# ADAS_schematic.net
KiCad netlist of a schematic drawn in EAGLE
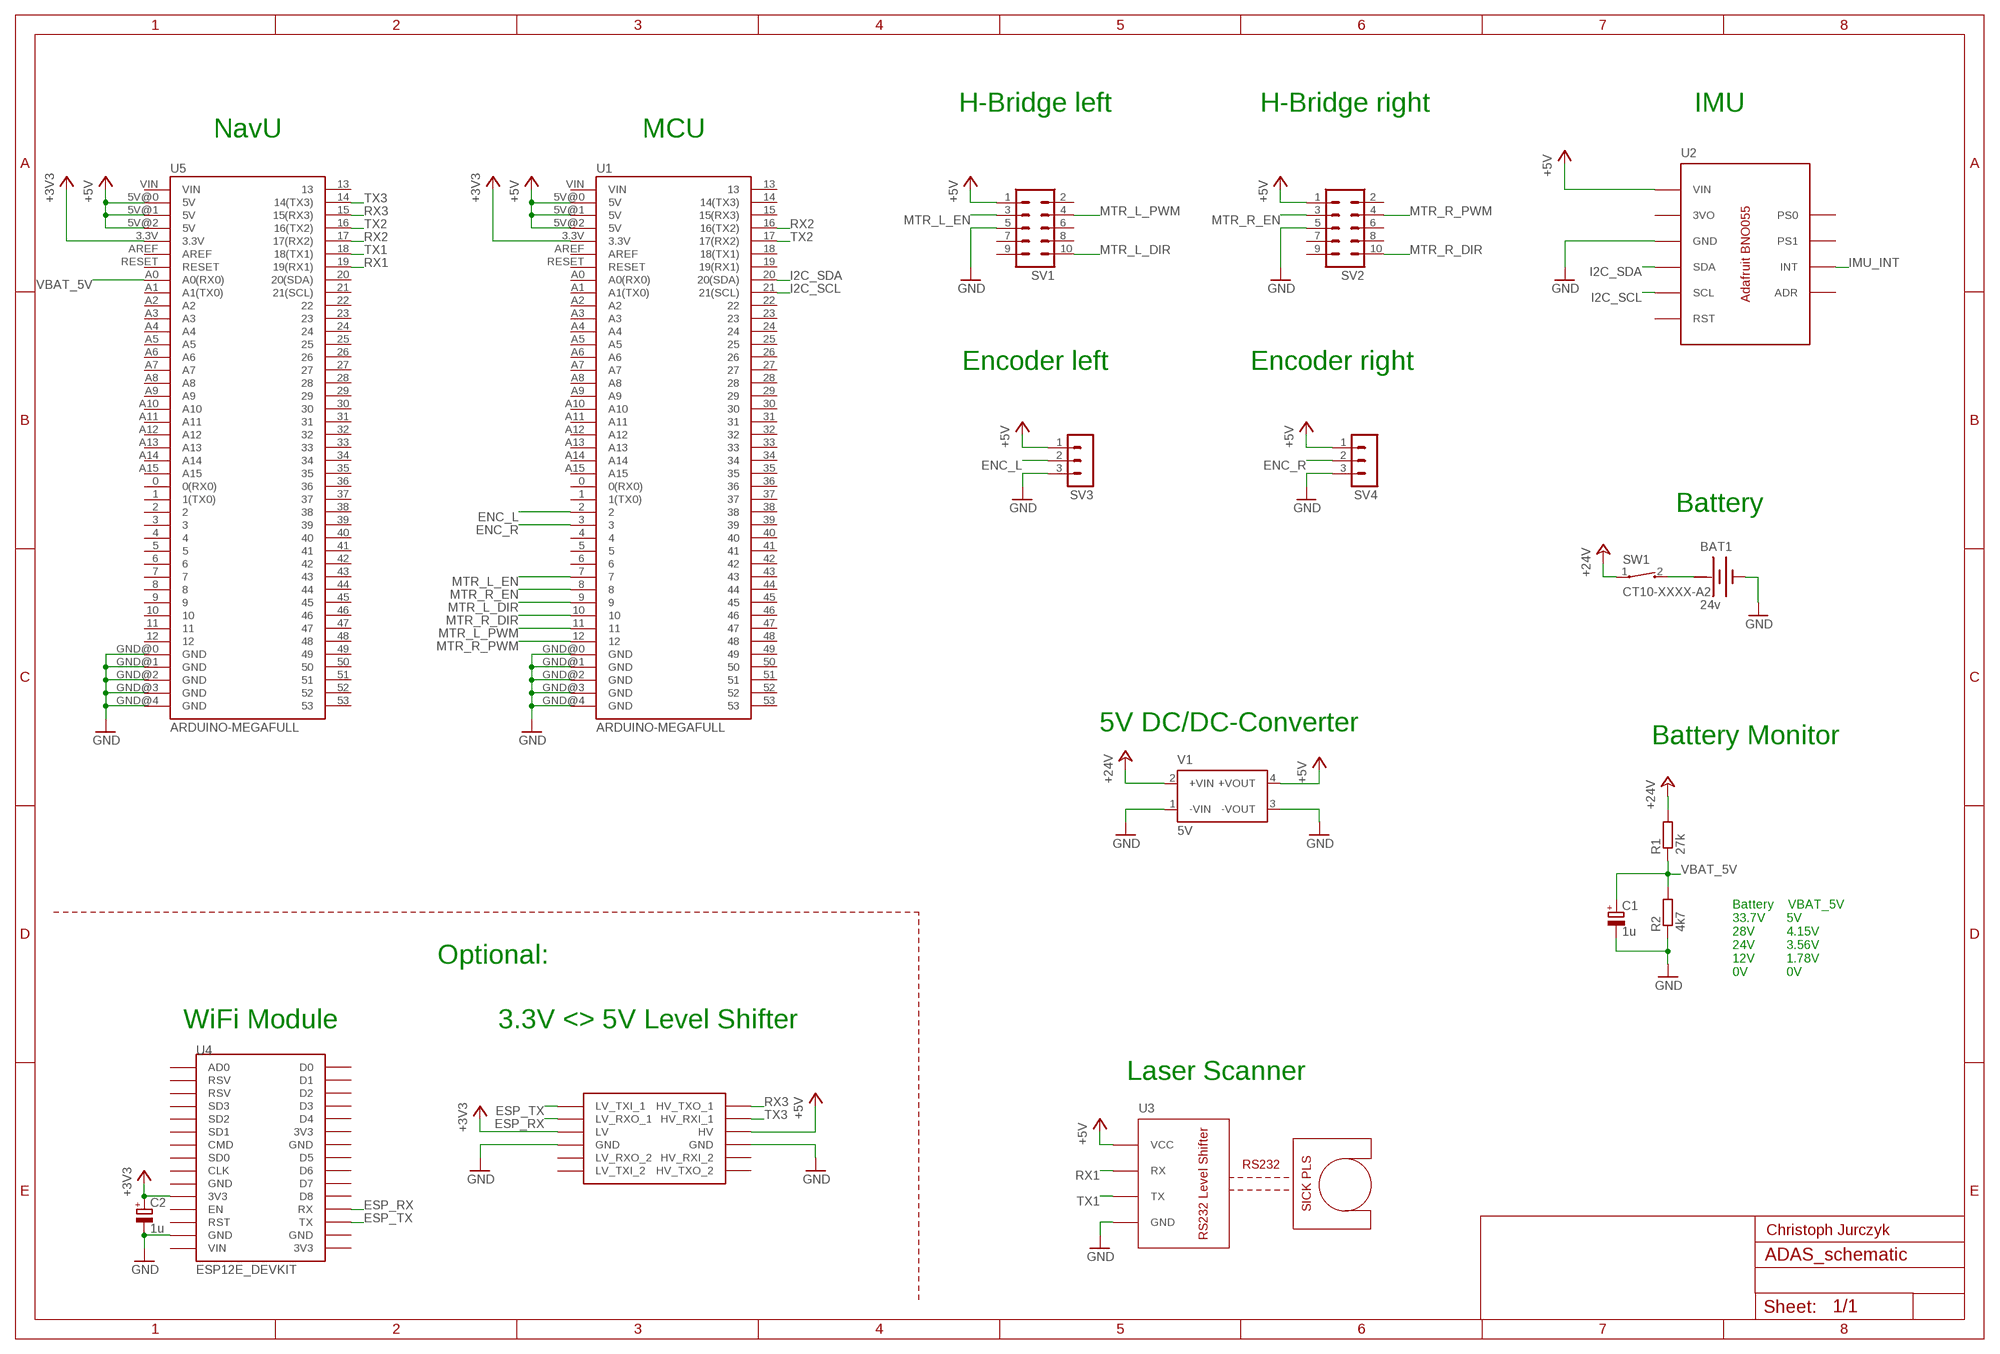
[diagram p0: schematic, sheet 1]

(export (version "E")
  (design (tool "Eeschema 10.0.6"))
  (components
    (comp (ref "BAT1")
      (value "24v")
      (footprint "eagle-import:BATTERY")
      (libsource (lib "eagle-import") (part "BATTERY"))
    )
    (comp (ref "C1")
      (value "1u")
      (footprint "eagle-import:139CLL-3R")
      (libsource (lib "eagle-import") (part "CPOL-EU139CLL-3R"))
    )
    (comp (ref "C2")
      (value "1u")
      (footprint "eagle-import:139CLL-3R")
      (libsource (lib "eagle-import") (part "CPOL-EU139CLL-3R"))
    )
    (comp (ref "R1")
      (value "27k")
      (footprint "eagle-import:0617_22")
      (libsource (lib "eagle-import") (part "R-EU_0617/22"))
    )
    (comp (ref "R2")
      (value "4k7")
      (footprint "eagle-import:0617_22")
      (libsource (lib "eagle-import") (part "R-EU_0617/22"))
    )
    (comp (ref "SV1")
      (value "ML10")
      (footprint "eagle-import:ML10")
      (libsource (lib "eagle-import") (part "ML10"))
    )
    (comp (ref "SV2")
      (value "ML10")
      (footprint "eagle-import:ML10")
      (libsource (lib "eagle-import") (part "ML10"))
    )
    (comp (ref "SV3")
      (value "MA03-1")
      (footprint "eagle-import:MA03-1")
      (libsource (lib "eagle-import") (part "MA03-1"))
    )
    (comp (ref "SV4")
      (value "MA03-1")
      (footprint "eagle-import:MA03-1")
      (libsource (lib "eagle-import") (part "MA03-1"))
    )
    (comp (ref "SW1")
      (value "CT10-XXXX-A2")
      (footprint "eagle-import:CT10-XXXX-A2")
      (libsource (lib "eagle-import") (part "CT10-XXXX-A2"))
    )
    (comp (ref "U$2")
      (value "LOGIC_LEVEL_CONVERTER")
      (footprint "eagle-import:LOGIC_LEVEL_CONVERTER")
      (libsource (lib "eagle-import") (part "LOGIC_LEVEL_CONVERTER"))
    )
    (comp (ref "U1")
      (value "ARDUINO-MEGAFULL")
      (footprint "eagle-import:ARDUINO_MEGA")
      (libsource (lib "eagle-import") (part "ARDUINO-MEGAFULL"))
    )
    (comp (ref "U2")
      (value "ADAFRUIT_BNO055")
      (footprint "eagle-import:DUMMY")
      (libsource (lib "eagle-import") (part "ADAFRUIT_BNO055"))
    )
    (comp (ref "U3")
      (value "SICK_PLS")
      (footprint "eagle-import:DUMMY")
      (libsource (lib "eagle-import") (part "SICK_PLS"))
    )
    (comp (ref "U4")
      (value "ESP12E_DEVKIT")
      (footprint "eagle-import:ESP12E_DEVKIT")
      (libsource (lib "eagle-import") (part "ESP12E_DEVKIT"))
    )
    (comp (ref "U5")
      (value "ARDUINO-MEGAFULL")
      (footprint "eagle-import:ARDUINO_MEGA")
      (libsource (lib "eagle-import") (part "ARDUINO-MEGAFULL"))
    )
    (comp (ref "V1")
      (value "5V")
      (footprint "eagle-import:TME")
      (fields (field (name "MPN") "TME 0505S"))
      (libsource (lib "eagle-import") (part "TME?0505S"))
    )
  )
  (nets
    (net (code "1") (name "+3V3") (class "Default")
      (node (ref "C2") (pin "+") (pinfunction "+_+") (pintype "passive"))
      (node (ref "U$2") (pin "P$3") (pinfunction "LV_P$3") (pintype "bidirectional"))
      (node (ref "U1") (pin "3.3V") (pinfunction "3.3V_3.3V") (pintype "bidirectional"))
      (node (ref "U4") (pin "3V3@0") (pinfunction "3V3_3V3@0") (pintype "bidirectional"))
      (node (ref "U5") (pin "3.3V") (pinfunction "3.3V_3.3V") (pintype "bidirectional"))
    )
    (net (code "2") (name "+5V") (class "Default")
      (node (ref "SV1") (pin "1") (pinfunction "1_1") (pintype "passive"))
      (node (ref "SV2") (pin "1") (pinfunction "1_1") (pintype "passive"))
      (node (ref "SV3") (pin "1") (pinfunction "1_1") (pintype "passive"))
      (node (ref "SV4") (pin "1") (pinfunction "1_1") (pintype "passive"))
      (node (ref "U$2") (pin "P$10") (pinfunction "HV_P$10") (pintype "bidirectional"))
      (node (ref "U1") (pin "5V@0") (pinfunction "5V_5V@0") (pintype "bidirectional"))
      (node (ref "U1") (pin "5V@1") (pinfunction "5V_5V@1") (pintype "bidirectional"))
      (node (ref "U1") (pin "5V@2") (pinfunction "5V_5V@2") (pintype "bidirectional"))
      (node (ref "U2") (pin "P$10") (pinfunction "VIN_P$10") (pintype "bidirectional"))
      (node (ref "U3") (pin "P$4") (pinfunction "VCC_P$4") (pintype "bidirectional"))
      (node (ref "U5") (pin "5V@0") (pinfunction "5V_5V@0") (pintype "bidirectional"))
      (node (ref "U5") (pin "5V@1") (pinfunction "5V_5V@1") (pintype "bidirectional"))
      (node (ref "U5") (pin "5V@2") (pinfunction "5V_5V@2") (pintype "bidirectional"))
      (node (ref "V1") (pin "4") (pinfunction "+VOUT_4") (pintype "passive"))
    )
    (net (code "3") (name "+24V") (class "Default")
      (node (ref "R1") (pin "2") (pinfunction "2_2") (pintype "passive"))
      (node (ref "SW1") (pin "1") (pinfunction "1_1") (pintype "passive"))
      (node (ref "V1") (pin "2") (pinfunction "+VIN_2") (pintype "passive"))
    )
    (net (code "4") (name "/+") (class "Default")
      (node (ref "BAT1") (pin "+@1") (pinfunction "+_+@1") (pintype "power_in"))
    )
    (net (code "5") (name "/ENC_L") (class "Default")
      (node (ref "SV3") (pin "2") (pinfunction "2_2") (pintype "passive"))
      (node (ref "U1") (pin "2") (pinfunction "2_2") (pintype "bidirectional"))
    )
    (net (code "6") (name "/ENC_R") (class "Default")
      (node (ref "SV4") (pin "2") (pinfunction "2_2") (pintype "passive"))
      (node (ref "U1") (pin "3") (pinfunction "3_3") (pintype "bidirectional"))
    )
    (net (code "7") (name "/ESP_RX") (class "Default")
      (node (ref "U$2") (pin "P$2") (pinfunction "LV_RXO_1_P$2") (pintype "bidirectional"))
      (node (ref "U4") (pin "RX") (pinfunction "RX_RX") (pintype "bidirectional"))
    )
    (net (code "8") (name "/ESP_TX") (class "Default")
      (node (ref "U$2") (pin "P$1") (pinfunction "LV_TXI_1_P$1") (pintype "bidirectional"))
      (node (ref "U4") (pin "TX") (pinfunction "TX_TX") (pintype "bidirectional"))
    )
    (net (code "9") (name "/I2C_SCL") (class "Default")
      (node (ref "U1") (pin "21") (pinfunction "21(SCL)_21") (pintype "bidirectional"))
      (node (ref "U2") (pin "P$8") (pinfunction "SCL_P$8") (pintype "bidirectional"))
    )
    (net (code "10") (name "/I2C_SDA") (class "Default")
      (node (ref "U1") (pin "20") (pinfunction "20(SDA)_20") (pintype "bidirectional"))
      (node (ref "U2") (pin "P$9") (pinfunction "SDA_P$9") (pintype "bidirectional"))
    )
    (net (code "11") (name "/IMU_INT") (class "Default")
      (node (ref "U2") (pin "P$4") (pinfunction "INT_P$4") (pintype "bidirectional"))
    )
    (net (code "12") (name "/MTR_L_DIR") (class "Default")
      (node (ref "SV1") (pin "10") (pinfunction "10_10") (pintype "passive"))
      (node (ref "U1") (pin "9") (pinfunction "9_9") (pintype "bidirectional"))
    )
    (net (code "13") (name "/MTR_L_EN") (class "Default")
      (node (ref "SV1") (pin "3") (pinfunction "3_3") (pintype "passive"))
      (node (ref "U1") (pin "7") (pinfunction "7_7") (pintype "bidirectional"))
    )
    (net (code "14") (name "/MTR_L_PWM") (class "Default")
      (node (ref "SV1") (pin "4") (pinfunction "4_4") (pintype "passive"))
      (node (ref "U1") (pin "11") (pinfunction "11_11") (pintype "bidirectional"))
    )
    (net (code "15") (name "/MTR_R_DIR") (class "Default")
      (node (ref "SV2") (pin "10") (pinfunction "10_10") (pintype "passive"))
      (node (ref "U1") (pin "10") (pinfunction "10_10") (pintype "bidirectional"))
    )
    (net (code "16") (name "/MTR_R_EN") (class "Default")
      (node (ref "SV2") (pin "3") (pinfunction "3_3") (pintype "passive"))
      (node (ref "U1") (pin "8") (pinfunction "8_8") (pintype "bidirectional"))
    )
    (net (code "17") (name "/MTR_R_PWM") (class "Default")
      (node (ref "SV2") (pin "4") (pinfunction "4_4") (pintype "passive"))
      (node (ref "U1") (pin "12") (pinfunction "12_12") (pintype "bidirectional"))
    )
    (net (code "18") (name "/RX1") (class "Default")
      (node (ref "U3") (pin "P$2") (pinfunction "RX_P$2") (pintype "bidirectional"))
      (node (ref "U5") (pin "19") (pinfunction "19(RX1)_19") (pintype "bidirectional"))
    )
    (net (code "19") (name "/RX2") (class "Default")
      (node (ref "U1") (pin "16") (pinfunction "16(TX2)_16") (pintype "bidirectional"))
      (node (ref "U5") (pin "17") (pinfunction "17(RX2)_17") (pintype "bidirectional"))
    )
    (net (code "20") (name "/RX3") (class "Default")
      (node (ref "U$2") (pin "P$12") (pinfunction "HV_TXO_1_P$12") (pintype "bidirectional"))
      (node (ref "U5") (pin "15") (pinfunction "15(RX3)_15") (pintype "bidirectional"))
    )
    (net (code "21") (name "/TX1") (class "Default")
      (node (ref "U3") (pin "P$3") (pinfunction "TX_P$3") (pintype "bidirectional"))
      (node (ref "U5") (pin "18") (pinfunction "18(TX1)_18") (pintype "bidirectional"))
    )
    (net (code "22") (name "/TX2") (class "Default")
      (node (ref "U1") (pin "17") (pinfunction "17(RX2)_17") (pintype "bidirectional"))
      (node (ref "U5") (pin "16") (pinfunction "16(TX2)_16") (pintype "bidirectional"))
    )
    (net (code "23") (name "/TX3") (class "Default")
      (node (ref "U$2") (pin "P$11") (pinfunction "HV_RXI_1_P$11") (pintype "bidirectional"))
      (node (ref "U5") (pin "14") (pinfunction "14(TX3)_14") (pintype "bidirectional"))
    )
    (net (code "24") (name "/VBAT_5V") (class "Default")
      (node (ref "C1") (pin "+") (pinfunction "+_+") (pintype "passive"))
      (node (ref "R1") (pin "1") (pinfunction "1_1") (pintype "passive"))
      (node (ref "R2") (pin "2") (pinfunction "2_2") (pintype "passive"))
      (node (ref "U5") (pin "A0") (pinfunction "A0(RX0)_A0") (pintype "bidirectional"))
    )
    (net (code "25") (name "GND") (class "Default")
      (node (ref "BAT1") (pin "-") (pinfunction "-_-") (pintype "power_in"))
      (node (ref "C1") (pin "-") (pinfunction "-_-") (pintype "passive"))
      (node (ref "C2") (pin "-") (pinfunction "-_-") (pintype "passive"))
      (node (ref "R2") (pin "1") (pinfunction "1_1") (pintype "passive"))
      (node (ref "SV1") (pin "5") (pinfunction "5_5") (pintype "passive"))
      (node (ref "SV2") (pin "5") (pinfunction "5_5") (pintype "passive"))
      (node (ref "SV3") (pin "3") (pinfunction "3_3") (pintype "passive"))
      (node (ref "SV4") (pin "3") (pinfunction "3_3") (pintype "passive"))
      (node (ref "U$2") (pin "P$4") (pinfunction "GND_P$4") (pintype "bidirectional"))
      (node (ref "U$2") (pin "P$9") (pinfunction "GND_P$9") (pintype "bidirectional"))
      (node (ref "U1") (pin "GND@0") (pinfunction "GND_GND@0") (pintype "bidirectional"))
      (node (ref "U1") (pin "GND@1") (pinfunction "GND_GND@1") (pintype "bidirectional"))
      (node (ref "U1") (pin "GND@2") (pinfunction "GND_GND@2") (pintype "bidirectional"))
      (node (ref "U1") (pin "GND@3") (pinfunction "GND_GND@3") (pintype "bidirectional"))
      (node (ref "U1") (pin "GND@4") (pinfunction "GND_GND@4") (pintype "bidirectional"))
      (node (ref "U2") (pin "P$3") (pinfunction "GND_P$3") (pintype "bidirectional"))
      (node (ref "U3") (pin "P$1") (pinfunction "GND_P$1") (pintype "bidirectional"))
      (node (ref "U4") (pin "GND@1") (pinfunction "GND_GND@1") (pintype "bidirectional"))
      (node (ref "U5") (pin "GND@0") (pinfunction "GND_GND@0") (pintype "bidirectional"))
      (node (ref "U5") (pin "GND@1") (pinfunction "GND_GND@1") (pintype "bidirectional"))
      (node (ref "U5") (pin "GND@2") (pinfunction "GND_GND@2") (pintype "bidirectional"))
      (node (ref "U5") (pin "GND@3") (pinfunction "GND_GND@3") (pintype "bidirectional"))
      (node (ref "U5") (pin "GND@4") (pinfunction "GND_GND@4") (pintype "bidirectional"))
      (node (ref "V1") (pin "1") (pinfunction "-VIN_1") (pintype "passive"))
      (node (ref "V1") (pin "3") (pinfunction "-VOUT_3") (pintype "passive"))
    )
    (net (code "26") (name "Net-(BAT1-Pad+)") (class "Default")
      (node (ref "BAT1") (pin "+") (pinfunction "+_+") (pintype "power_in"))
      (node (ref "SW1") (pin "2") (pinfunction "2_2") (pintype "passive"))
    )
    (net (code "27") (name "unconnected-(SV1-Pad2)") (class "Default")
      (node (ref "SV1") (pin "2") (pinfunction "2_2") (pintype "passive"))
    )
    (net (code "28") (name "unconnected-(SV1-Pad6)") (class "Default")
      (node (ref "SV1") (pin "6") (pinfunction "6_6") (pintype "passive"))
    )
    (net (code "29") (name "unconnected-(SV1-Pad7)") (class "Default")
      (node (ref "SV1") (pin "7") (pinfunction "7_7") (pintype "passive"))
    )
    (net (code "30") (name "unconnected-(SV1-Pad8)") (class "Default")
      (node (ref "SV1") (pin "8") (pinfunction "8_8") (pintype "passive"))
    )
    (net (code "31") (name "unconnected-(SV1-Pad9)") (class "Default")
      (node (ref "SV1") (pin "9") (pinfunction "9_9") (pintype "passive"))
    )
    (net (code "32") (name "unconnected-(SV2-Pad2)") (class "Default")
      (node (ref "SV2") (pin "2") (pinfunction "2_2") (pintype "passive"))
    )
    (net (code "33") (name "unconnected-(SV2-Pad6)") (class "Default")
      (node (ref "SV2") (pin "6") (pinfunction "6_6") (pintype "passive"))
    )
    (net (code "34") (name "unconnected-(SV2-Pad7)") (class "Default")
      (node (ref "SV2") (pin "7") (pinfunction "7_7") (pintype "passive"))
    )
    (net (code "35") (name "unconnected-(SV2-Pad8)") (class "Default")
      (node (ref "SV2") (pin "8") (pinfunction "8_8") (pintype "passive"))
    )
    (net (code "36") (name "unconnected-(SV2-Pad9)") (class "Default")
      (node (ref "SV2") (pin "9") (pinfunction "9_9") (pintype "passive"))
    )
    (net (code "37") (name "unconnected-(U$2-HV_RXI_2-PadP$8)") (class "Default")
      (node (ref "U$2") (pin "P$8") (pinfunction "HV_RXI_2_P$8") (pintype "bidirectional"))
    )
    (net (code "38") (name "unconnected-(U$2-HV_TXO_2-PadP$7)") (class "Default")
      (node (ref "U$2") (pin "P$7") (pinfunction "HV_TXO_2_P$7") (pintype "bidirectional"))
    )
    (net (code "39") (name "unconnected-(U$2-LV_RXO_2-PadP$5)") (class "Default")
      (node (ref "U$2") (pin "P$5") (pinfunction "LV_RXO_2_P$5") (pintype "bidirectional"))
    )
    (net (code "40") (name "unconnected-(U$2-LV_TXI_2-PadP$6)") (class "Default")
      (node (ref "U$2") (pin "P$6") (pinfunction "LV_TXI_2_P$6") (pintype "bidirectional"))
    )
    (net (code "41") (name "unconnected-(U1-0(RX0)-Pad0)") (class "Default")
      (node (ref "U1") (pin "0") (pinfunction "0(RX0)_0") (pintype "bidirectional"))
    )
    (net (code "42") (name "unconnected-(U1-1(TX0)-Pad1)") (class "Default")
      (node (ref "U1") (pin "1") (pinfunction "1(TX0)_1") (pintype "bidirectional"))
    )
    (net (code "43") (name "unconnected-(U1-14(TX3)-Pad14)") (class "Default")
      (node (ref "U1") (pin "14") (pinfunction "14(TX3)_14") (pintype "bidirectional"))
    )
    (net (code "44") (name "unconnected-(U1-15(RX3)-Pad15)") (class "Default")
      (node (ref "U1") (pin "15") (pinfunction "15(RX3)_15") (pintype "bidirectional"))
    )
    (net (code "45") (name "unconnected-(U1-18(TX1)-Pad18)") (class "Default")
      (node (ref "U1") (pin "18") (pinfunction "18(TX1)_18") (pintype "bidirectional"))
    )
    (net (code "46") (name "unconnected-(U1-19(RX1)-Pad19)") (class "Default")
      (node (ref "U1") (pin "19") (pinfunction "19(RX1)_19") (pintype "bidirectional"))
    )
    (net (code "47") (name "unconnected-(U1-A0(RX0)-PadA0)") (class "Default")
      (node (ref "U1") (pin "A0") (pinfunction "A0(RX0)_A0") (pintype "bidirectional"))
    )
    (net (code "48") (name "unconnected-(U1-A1(TX0)-PadA1)") (class "Default")
      (node (ref "U1") (pin "A1") (pinfunction "A1(TX0)_A1") (pintype "bidirectional"))
    )
    (net (code "49") (name "unconnected-(U1-Pad4)") (class "Default")
      (node (ref "U1") (pin "4") (pinfunction "4_4") (pintype "bidirectional"))
    )
    (net (code "50") (name "unconnected-(U1-Pad5)") (class "Default")
      (node (ref "U1") (pin "5") (pinfunction "5_5") (pintype "bidirectional"))
    )
    (net (code "51") (name "unconnected-(U1-Pad6)") (class "Default")
      (node (ref "U1") (pin "6") (pinfunction "6_6") (pintype "bidirectional"))
    )
    (net (code "52") (name "unconnected-(U1-Pad13)") (class "Default")
      (node (ref "U1") (pin "13") (pinfunction "13_13") (pintype "bidirectional"))
    )
    (net (code "53") (name "unconnected-(U1-Pad22)") (class "Default")
      (node (ref "U1") (pin "22") (pinfunction "22_22") (pintype "bidirectional"))
    )
    (net (code "54") (name "unconnected-(U1-Pad23)") (class "Default")
      (node (ref "U1") (pin "23") (pinfunction "23_23") (pintype "bidirectional"))
    )
    (net (code "55") (name "unconnected-(U1-Pad24)") (class "Default")
      (node (ref "U1") (pin "24") (pinfunction "24_24") (pintype "bidirectional"))
    )
    (net (code "56") (name "unconnected-(U1-Pad25)") (class "Default")
      (node (ref "U1") (pin "25") (pinfunction "25_25") (pintype "bidirectional"))
    )
    (net (code "57") (name "unconnected-(U1-Pad26)") (class "Default")
      (node (ref "U1") (pin "26") (pinfunction "26_26") (pintype "bidirectional"))
    )
    (net (code "58") (name "unconnected-(U1-Pad27)") (class "Default")
      (node (ref "U1") (pin "27") (pinfunction "27_27") (pintype "bidirectional"))
    )
    (net (code "59") (name "unconnected-(U1-Pad28)") (class "Default")
      (node (ref "U1") (pin "28") (pinfunction "28_28") (pintype "bidirectional"))
    )
    (net (code "60") (name "unconnected-(U1-Pad29)") (class "Default")
      (node (ref "U1") (pin "29") (pinfunction "29_29") (pintype "bidirectional"))
    )
    (net (code "61") (name "unconnected-(U1-Pad30)") (class "Default")
      (node (ref "U1") (pin "30") (pinfunction "30_30") (pintype "bidirectional"))
    )
    (net (code "62") (name "unconnected-(U1-Pad31)") (class "Default")
      (node (ref "U1") (pin "31") (pinfunction "31_31") (pintype "bidirectional"))
    )
    (net (code "63") (name "unconnected-(U1-Pad32)") (class "Default")
      (node (ref "U1") (pin "32") (pinfunction "32_32") (pintype "bidirectional"))
    )
    (net (code "64") (name "unconnected-(U1-Pad33)") (class "Default")
      (node (ref "U1") (pin "33") (pinfunction "33_33") (pintype "bidirectional"))
    )
    (net (code "65") (name "unconnected-(U1-Pad34)") (class "Default")
      (node (ref "U1") (pin "34") (pinfunction "34_34") (pintype "bidirectional"))
    )
    (net (code "66") (name "unconnected-(U1-Pad35)") (class "Default")
      (node (ref "U1") (pin "35") (pinfunction "35_35") (pintype "bidirectional"))
    )
    (net (code "67") (name "unconnected-(U1-Pad36)") (class "Default")
      (node (ref "U1") (pin "36") (pinfunction "36_36") (pintype "bidirectional"))
    )
    (net (code "68") (name "unconnected-(U1-Pad37)") (class "Default")
      (node (ref "U1") (pin "37") (pinfunction "37_37") (pintype "bidirectional"))
    )
    (net (code "69") (name "unconnected-(U1-Pad38)") (class "Default")
      (node (ref "U1") (pin "38") (pinfunction "38_38") (pintype "bidirectional"))
    )
    (net (code "70") (name "unconnected-(U1-Pad39)") (class "Default")
      (node (ref "U1") (pin "39") (pinfunction "39_39") (pintype "bidirectional"))
    )
    (net (code "71") (name "unconnected-(U1-Pad40)") (class "Default")
      (node (ref "U1") (pin "40") (pinfunction "40_40") (pintype "bidirectional"))
    )
    (net (code "72") (name "unconnected-(U1-Pad41)") (class "Default")
      (node (ref "U1") (pin "41") (pinfunction "41_41") (pintype "bidirectional"))
    )
    (net (code "73") (name "unconnected-(U1-Pad42)") (class "Default")
      (node (ref "U1") (pin "42") (pinfunction "42_42") (pintype "bidirectional"))
    )
    (net (code "74") (name "unconnected-(U1-Pad43)") (class "Default")
      (node (ref "U1") (pin "43") (pinfunction "43_43") (pintype "bidirectional"))
    )
    (net (code "75") (name "unconnected-(U1-Pad44)") (class "Default")
      (node (ref "U1") (pin "44") (pinfunction "44_44") (pintype "bidirectional"))
    )
    (net (code "76") (name "unconnected-(U1-Pad45)") (class "Default")
      (node (ref "U1") (pin "45") (pinfunction "45_45") (pintype "bidirectional"))
    )
    (net (code "77") (name "unconnected-(U1-Pad46)") (class "Default")
      (node (ref "U1") (pin "46") (pinfunction "46_46") (pintype "bidirectional"))
    )
    (net (code "78") (name "unconnected-(U1-Pad47)") (class "Default")
      (node (ref "U1") (pin "47") (pinfunction "47_47") (pintype "bidirectional"))
    )
    (net (code "79") (name "unconnected-(U1-Pad48)") (class "Default")
      (node (ref "U1") (pin "48") (pinfunction "48_48") (pintype "bidirectional"))
    )
    (net (code "80") (name "unconnected-(U1-Pad49)") (class "Default")
      (node (ref "U1") (pin "49") (pinfunction "49_49") (pintype "bidirectional"))
    )
    (net (code "81") (name "unconnected-(U1-Pad50)") (class "Default")
      (node (ref "U1") (pin "50") (pinfunction "50_50") (pintype "bidirectional"))
    )
    (net (code "82") (name "unconnected-(U1-Pad51)") (class "Default")
      (node (ref "U1") (pin "51") (pinfunction "51_51") (pintype "bidirectional"))
    )
    (net (code "83") (name "unconnected-(U1-Pad52)") (class "Default")
      (node (ref "U1") (pin "52") (pinfunction "52_52") (pintype "bidirectional"))
    )
    (net (code "84") (name "unconnected-(U1-Pad53)") (class "Default")
      (node (ref "U1") (pin "53") (pinfunction "53_53") (pintype "bidirectional"))
    )
    (net (code "85") (name "unconnected-(U1-PadA2)") (class "Default")
      (node (ref "U1") (pin "A2") (pinfunction "A2_A2") (pintype "bidirectional"))
    )
    (net (code "86") (name "unconnected-(U1-PadA3)") (class "Default")
      (node (ref "U1") (pin "A3") (pinfunction "A3_A3") (pintype "bidirectional"))
    )
    (net (code "87") (name "unconnected-(U1-PadA4)") (class "Default")
      (node (ref "U1") (pin "A4") (pinfunction "A4_A4") (pintype "bidirectional"))
    )
    (net (code "88") (name "unconnected-(U1-PadA5)") (class "Default")
      (node (ref "U1") (pin "A5") (pinfunction "A5_A5") (pintype "bidirectional"))
    )
    (net (code "89") (name "unconnected-(U1-PadA6)") (class "Default")
      (node (ref "U1") (pin "A6") (pinfunction "A6_A6") (pintype "bidirectional"))
    )
    (net (code "90") (name "unconnected-(U1-PadA7)") (class "Default")
      (node (ref "U1") (pin "A7") (pinfunction "A7_A7") (pintype "bidirectional"))
    )
    (net (code "91") (name "unconnected-(U1-PadA8)") (class "Default")
      (node (ref "U1") (pin "A8") (pinfunction "A8_A8") (pintype "bidirectional"))
    )
    (net (code "92") (name "unconnected-(U1-PadA9)") (class "Default")
      (node (ref "U1") (pin "A9") (pinfunction "A9_A9") (pintype "bidirectional"))
    )
    (net (code "93") (name "unconnected-(U1-PadA10)") (class "Default")
      (node (ref "U1") (pin "A10") (pinfunction "A10_A10") (pintype "bidirectional"))
    )
    (net (code "94") (name "unconnected-(U1-PadA11)") (class "Default")
      (node (ref "U1") (pin "A11") (pinfunction "A11_A11") (pintype "bidirectional"))
    )
    (net (code "95") (name "unconnected-(U1-PadA12)") (class "Default")
      (node (ref "U1") (pin "A12") (pinfunction "A12_A12") (pintype "bidirectional"))
    )
    (net (code "96") (name "unconnected-(U1-PadA13)") (class "Default")
      (node (ref "U1") (pin "A13") (pinfunction "A13_A13") (pintype "bidirectional"))
    )
    (net (code "97") (name "unconnected-(U1-PadA14)") (class "Default")
      (node (ref "U1") (pin "A14") (pinfunction "A14_A14") (pintype "bidirectional"))
    )
    (net (code "98") (name "unconnected-(U1-PadA15)") (class "Default")
      (node (ref "U1") (pin "A15") (pinfunction "A15_A15") (pintype "bidirectional"))
    )
    (net (code "99") (name "unconnected-(U1-PadAREF)") (class "Default")
      (node (ref "U1") (pin "AREF") (pinfunction "AREF_AREF") (pintype "bidirectional"))
    )
    (net (code "100") (name "unconnected-(U1-PadRESET)") (class "Default")
      (node (ref "U1") (pin "RESET") (pinfunction "RESET_RESET") (pintype "bidirectional"))
    )
    (net (code "101") (name "unconnected-(U1-PadVIN)") (class "Default")
      (node (ref "U1") (pin "VIN") (pinfunction "VIN_VIN") (pintype "bidirectional"))
    )
    (net (code "102") (name "unconnected-(U2-3VO-PadP$1)") (class "Default")
      (node (ref "U2") (pin "P$1") (pinfunction "3VO_P$1") (pintype "bidirectional"))
    )
    (net (code "103") (name "unconnected-(U2-ADR-PadP$2)") (class "Default")
      (node (ref "U2") (pin "P$2") (pinfunction "ADR_P$2") (pintype "bidirectional"))
    )
    (net (code "104") (name "unconnected-(U2-PS0-PadP$5)") (class "Default")
      (node (ref "U2") (pin "P$5") (pinfunction "PS0_P$5") (pintype "bidirectional"))
    )
    (net (code "105") (name "unconnected-(U2-PS1-PadP$6)") (class "Default")
      (node (ref "U2") (pin "P$6") (pinfunction "PS1_P$6") (pintype "bidirectional"))
    )
    (net (code "106") (name "unconnected-(U2-RST-PadP$7)") (class "Default")
      (node (ref "U2") (pin "P$7") (pinfunction "RST_P$7") (pintype "bidirectional"))
    )
    (net (code "107") (name "unconnected-(U4-3V3-Pad3V3@1)") (class "Default")
      (node (ref "U4") (pin "3V3@1") (pinfunction "3V3_3V3@1") (pintype "bidirectional"))
    )
    (net (code "108") (name "unconnected-(U4-3V3-Pad3V3@2)") (class "Default")
      (node (ref "U4") (pin "3V3@2") (pinfunction "3V3_3V3@2") (pintype "bidirectional"))
    )
    (net (code "109") (name "unconnected-(U4-GND-PadGND@0)") (class "Default")
      (node (ref "U4") (pin "GND@0") (pinfunction "GND_GND@0") (pintype "bidirectional"))
    )
    (net (code "110") (name "unconnected-(U4-GND-PadGND@2)") (class "Default")
      (node (ref "U4") (pin "GND@2") (pinfunction "GND_GND@2") (pintype "bidirectional"))
    )
    (net (code "111") (name "unconnected-(U4-GND-PadGND@3)") (class "Default")
      (node (ref "U4") (pin "GND@3") (pinfunction "GND_GND@3") (pintype "bidirectional"))
    )
    (net (code "112") (name "unconnected-(U4-PadAD0)") (class "Default")
      (node (ref "U4") (pin "AD0") (pinfunction "AD0_AD0") (pintype "bidirectional"))
    )
    (net (code "113") (name "unconnected-(U4-PadCLK)") (class "Default")
      (node (ref "U4") (pin "CLK") (pinfunction "CLK_CLK") (pintype "bidirectional"))
    )
    (net (code "114") (name "unconnected-(U4-PadCMD)") (class "Default")
      (node (ref "U4") (pin "CMD") (pinfunction "CMD_CMD") (pintype "bidirectional"))
    )
    (net (code "115") (name "unconnected-(U4-PadD0)") (class "Default")
      (node (ref "U4") (pin "D0") (pinfunction "D0_D0") (pintype "bidirectional"))
    )
    (net (code "116") (name "unconnected-(U4-PadD1)") (class "Default")
      (node (ref "U4") (pin "D1") (pinfunction "D1_D1") (pintype "bidirectional"))
    )
    (net (code "117") (name "unconnected-(U4-PadD2)") (class "Default")
      (node (ref "U4") (pin "D2") (pinfunction "D2_D2") (pintype "bidirectional"))
    )
    (net (code "118") (name "unconnected-(U4-PadD3)") (class "Default")
      (node (ref "U4") (pin "D3") (pinfunction "D3_D3") (pintype "bidirectional"))
    )
    (net (code "119") (name "unconnected-(U4-PadD4)") (class "Default")
      (node (ref "U4") (pin "D4") (pinfunction "D4_D4") (pintype "bidirectional"))
    )
    (net (code "120") (name "unconnected-(U4-PadD5)") (class "Default")
      (node (ref "U4") (pin "D5") (pinfunction "D5_D5") (pintype "bidirectional"))
    )
    (net (code "121") (name "unconnected-(U4-PadD6)") (class "Default")
      (node (ref "U4") (pin "D6") (pinfunction "D6_D6") (pintype "bidirectional"))
    )
    (net (code "122") (name "unconnected-(U4-PadD7)") (class "Default")
      (node (ref "U4") (pin "D7") (pinfunction "D7_D7") (pintype "bidirectional"))
    )
    (net (code "123") (name "unconnected-(U4-PadD8)") (class "Default")
      (node (ref "U4") (pin "D8") (pinfunction "D8_D8") (pintype "bidirectional"))
    )
    (net (code "124") (name "unconnected-(U4-PadEN)") (class "Default")
      (node (ref "U4") (pin "EN") (pinfunction "EN_EN") (pintype "bidirectional"))
    )
    (net (code "125") (name "unconnected-(U4-PadRST)") (class "Default")
      (node (ref "U4") (pin "RST") (pinfunction "RST_RST") (pintype "bidirectional"))
    )
    (net (code "126") (name "unconnected-(U4-PadSD0)") (class "Default")
      (node (ref "U4") (pin "SD0") (pinfunction "SD0_SD0") (pintype "bidirectional"))
    )
    (net (code "127") (name "unconnected-(U4-PadSD1)") (class "Default")
      (node (ref "U4") (pin "SD1") (pinfunction "SD1_SD1") (pintype "bidirectional"))
    )
    (net (code "128") (name "unconnected-(U4-PadSD2)") (class "Default")
      (node (ref "U4") (pin "SD2") (pinfunction "SD2_SD2") (pintype "bidirectional"))
    )
    (net (code "129") (name "unconnected-(U4-PadSD3)") (class "Default")
      (node (ref "U4") (pin "SD3") (pinfunction "SD3_SD3") (pintype "bidirectional"))
    )
    (net (code "130") (name "unconnected-(U4-PadVIN)") (class "Default")
      (node (ref "U4") (pin "VIN") (pinfunction "VIN_VIN") (pintype "bidirectional"))
    )
    (net (code "131") (name "unconnected-(U4-RSV-PadRSV@0)") (class "Default")
      (node (ref "U4") (pin "RSV@0") (pinfunction "RSV_RSV@0") (pintype "bidirectional"))
    )
    (net (code "132") (name "unconnected-(U4-RSV-PadRSV@1)") (class "Default")
      (node (ref "U4") (pin "RSV@1") (pinfunction "RSV_RSV@1") (pintype "bidirectional"))
    )
    (net (code "133") (name "unconnected-(U5-0(RX0)-Pad0)") (class "Default")
      (node (ref "U5") (pin "0") (pinfunction "0(RX0)_0") (pintype "bidirectional"))
    )
    (net (code "134") (name "unconnected-(U5-1(TX0)-Pad1)") (class "Default")
      (node (ref "U5") (pin "1") (pinfunction "1(TX0)_1") (pintype "bidirectional"))
    )
    (net (code "135") (name "unconnected-(U5-20(SDA)-Pad20)") (class "Default")
      (node (ref "U5") (pin "20") (pinfunction "20(SDA)_20") (pintype "bidirectional"))
    )
    (net (code "136") (name "unconnected-(U5-21(SCL)-Pad21)") (class "Default")
      (node (ref "U5") (pin "21") (pinfunction "21(SCL)_21") (pintype "bidirectional"))
    )
    (net (code "137") (name "unconnected-(U5-A1(TX0)-PadA1)") (class "Default")
      (node (ref "U5") (pin "A1") (pinfunction "A1(TX0)_A1") (pintype "bidirectional"))
    )
    (net (code "138") (name "unconnected-(U5-Pad2)") (class "Default")
      (node (ref "U5") (pin "2") (pinfunction "2_2") (pintype "bidirectional"))
    )
    (net (code "139") (name "unconnected-(U5-Pad3)") (class "Default")
      (node (ref "U5") (pin "3") (pinfunction "3_3") (pintype "bidirectional"))
    )
    (net (code "140") (name "unconnected-(U5-Pad4)") (class "Default")
      (node (ref "U5") (pin "4") (pinfunction "4_4") (pintype "bidirectional"))
    )
    (net (code "141") (name "unconnected-(U5-Pad5)") (class "Default")
      (node (ref "U5") (pin "5") (pinfunction "5_5") (pintype "bidirectional"))
    )
    (net (code "142") (name "unconnected-(U5-Pad6)") (class "Default")
      (node (ref "U5") (pin "6") (pinfunction "6_6") (pintype "bidirectional"))
    )
    (net (code "143") (name "unconnected-(U5-Pad7)") (class "Default")
      (node (ref "U5") (pin "7") (pinfunction "7_7") (pintype "bidirectional"))
    )
    (net (code "144") (name "unconnected-(U5-Pad8)") (class "Default")
      (node (ref "U5") (pin "8") (pinfunction "8_8") (pintype "bidirectional"))
    )
    (net (code "145") (name "unconnected-(U5-Pad9)") (class "Default")
      (node (ref "U5") (pin "9") (pinfunction "9_9") (pintype "bidirectional"))
    )
    (net (code "146") (name "unconnected-(U5-Pad10)") (class "Default")
      (node (ref "U5") (pin "10") (pinfunction "10_10") (pintype "bidirectional"))
    )
    (net (code "147") (name "unconnected-(U5-Pad11)") (class "Default")
      (node (ref "U5") (pin "11") (pinfunction "11_11") (pintype "bidirectional"))
    )
    (net (code "148") (name "unconnected-(U5-Pad12)") (class "Default")
      (node (ref "U5") (pin "12") (pinfunction "12_12") (pintype "bidirectional"))
    )
    (net (code "149") (name "unconnected-(U5-Pad13)") (class "Default")
      (node (ref "U5") (pin "13") (pinfunction "13_13") (pintype "bidirectional"))
    )
    (net (code "150") (name "unconnected-(U5-Pad22)") (class "Default")
      (node (ref "U5") (pin "22") (pinfunction "22_22") (pintype "bidirectional"))
    )
    (net (code "151") (name "unconnected-(U5-Pad23)") (class "Default")
      (node (ref "U5") (pin "23") (pinfunction "23_23") (pintype "bidirectional"))
    )
    (net (code "152") (name "unconnected-(U5-Pad24)") (class "Default")
      (node (ref "U5") (pin "24") (pinfunction "24_24") (pintype "bidirectional"))
    )
    (net (code "153") (name "unconnected-(U5-Pad25)") (class "Default")
      (node (ref "U5") (pin "25") (pinfunction "25_25") (pintype "bidirectional"))
    )
    (net (code "154") (name "unconnected-(U5-Pad26)") (class "Default")
      (node (ref "U5") (pin "26") (pinfunction "26_26") (pintype "bidirectional"))
    )
    (net (code "155") (name "unconnected-(U5-Pad27)") (class "Default")
      (node (ref "U5") (pin "27") (pinfunction "27_27") (pintype "bidirectional"))
    )
    (net (code "156") (name "unconnected-(U5-Pad28)") (class "Default")
      (node (ref "U5") (pin "28") (pinfunction "28_28") (pintype "bidirectional"))
    )
    (net (code "157") (name "unconnected-(U5-Pad29)") (class "Default")
      (node (ref "U5") (pin "29") (pinfunction "29_29") (pintype "bidirectional"))
    )
    (net (code "158") (name "unconnected-(U5-Pad30)") (class "Default")
      (node (ref "U5") (pin "30") (pinfunction "30_30") (pintype "bidirectional"))
    )
    (net (code "159") (name "unconnected-(U5-Pad31)") (class "Default")
      (node (ref "U5") (pin "31") (pinfunction "31_31") (pintype "bidirectional"))
    )
    (net (code "160") (name "unconnected-(U5-Pad32)") (class "Default")
      (node (ref "U5") (pin "32") (pinfunction "32_32") (pintype "bidirectional"))
    )
    (net (code "161") (name "unconnected-(U5-Pad33)") (class "Default")
      (node (ref "U5") (pin "33") (pinfunction "33_33") (pintype "bidirectional"))
    )
    (net (code "162") (name "unconnected-(U5-Pad34)") (class "Default")
      (node (ref "U5") (pin "34") (pinfunction "34_34") (pintype "bidirectional"))
    )
    (net (code "163") (name "unconnected-(U5-Pad35)") (class "Default")
      (node (ref "U5") (pin "35") (pinfunction "35_35") (pintype "bidirectional"))
    )
    (net (code "164") (name "unconnected-(U5-Pad36)") (class "Default")
      (node (ref "U5") (pin "36") (pinfunction "36_36") (pintype "bidirectional"))
    )
    (net (code "165") (name "unconnected-(U5-Pad37)") (class "Default")
      (node (ref "U5") (pin "37") (pinfunction "37_37") (pintype "bidirectional"))
    )
    (net (code "166") (name "unconnected-(U5-Pad38)") (class "Default")
      (node (ref "U5") (pin "38") (pinfunction "38_38") (pintype "bidirectional"))
    )
    (net (code "167") (name "unconnected-(U5-Pad39)") (class "Default")
      (node (ref "U5") (pin "39") (pinfunction "39_39") (pintype "bidirectional"))
    )
    (net (code "168") (name "unconnected-(U5-Pad40)") (class "Default")
      (node (ref "U5") (pin "40") (pinfunction "40_40") (pintype "bidirectional"))
    )
    (net (code "169") (name "unconnected-(U5-Pad41)") (class "Default")
      (node (ref "U5") (pin "41") (pinfunction "41_41") (pintype "bidirectional"))
    )
    (net (code "170") (name "unconnected-(U5-Pad42)") (class "Default")
      (node (ref "U5") (pin "42") (pinfunction "42_42") (pintype "bidirectional"))
    )
    (net (code "171") (name "unconnected-(U5-Pad43)") (class "Default")
      (node (ref "U5") (pin "43") (pinfunction "43_43") (pintype "bidirectional"))
    )
    (net (code "172") (name "unconnected-(U5-Pad44)") (class "Default")
      (node (ref "U5") (pin "44") (pinfunction "44_44") (pintype "bidirectional"))
    )
    (net (code "173") (name "unconnected-(U5-Pad45)") (class "Default")
      (node (ref "U5") (pin "45") (pinfunction "45_45") (pintype "bidirectional"))
    )
    (net (code "174") (name "unconnected-(U5-Pad46)") (class "Default")
      (node (ref "U5") (pin "46") (pinfunction "46_46") (pintype "bidirectional"))
    )
    (net (code "175") (name "unconnected-(U5-Pad47)") (class "Default")
      (node (ref "U5") (pin "47") (pinfunction "47_47") (pintype "bidirectional"))
    )
    (net (code "176") (name "unconnected-(U5-Pad48)") (class "Default")
      (node (ref "U5") (pin "48") (pinfunction "48_48") (pintype "bidirectional"))
    )
    (net (code "177") (name "unconnected-(U5-Pad49)") (class "Default")
      (node (ref "U5") (pin "49") (pinfunction "49_49") (pintype "bidirectional"))
    )
    (net (code "178") (name "unconnected-(U5-Pad50)") (class "Default")
      (node (ref "U5") (pin "50") (pinfunction "50_50") (pintype "bidirectional"))
    )
    (net (code "179") (name "unconnected-(U5-Pad51)") (class "Default")
      (node (ref "U5") (pin "51") (pinfunction "51_51") (pintype "bidirectional"))
    )
    (net (code "180") (name "unconnected-(U5-Pad52)") (class "Default")
      (node (ref "U5") (pin "52") (pinfunction "52_52") (pintype "bidirectional"))
    )
    (net (code "181") (name "unconnected-(U5-Pad53)") (class "Default")
      (node (ref "U5") (pin "53") (pinfunction "53_53") (pintype "bidirectional"))
    )
    (net (code "182") (name "unconnected-(U5-PadA2)") (class "Default")
      (node (ref "U5") (pin "A2") (pinfunction "A2_A2") (pintype "bidirectional"))
    )
    (net (code "183") (name "unconnected-(U5-PadA3)") (class "Default")
      (node (ref "U5") (pin "A3") (pinfunction "A3_A3") (pintype "bidirectional"))
    )
    (net (code "184") (name "unconnected-(U5-PadA4)") (class "Default")
      (node (ref "U5") (pin "A4") (pinfunction "A4_A4") (pintype "bidirectional"))
    )
    (net (code "185") (name "unconnected-(U5-PadA5)") (class "Default")
      (node (ref "U5") (pin "A5") (pinfunction "A5_A5") (pintype "bidirectional"))
    )
    (net (code "186") (name "unconnected-(U5-PadA6)") (class "Default")
      (node (ref "U5") (pin "A6") (pinfunction "A6_A6") (pintype "bidirectional"))
    )
    (net (code "187") (name "unconnected-(U5-PadA7)") (class "Default")
      (node (ref "U5") (pin "A7") (pinfunction "A7_A7") (pintype "bidirectional"))
    )
    (net (code "188") (name "unconnected-(U5-PadA8)") (class "Default")
      (node (ref "U5") (pin "A8") (pinfunction "A8_A8") (pintype "bidirectional"))
    )
    (net (code "189") (name "unconnected-(U5-PadA9)") (class "Default")
      (node (ref "U5") (pin "A9") (pinfunction "A9_A9") (pintype "bidirectional"))
    )
    (net (code "190") (name "unconnected-(U5-PadA10)") (class "Default")
      (node (ref "U5") (pin "A10") (pinfunction "A10_A10") (pintype "bidirectional"))
    )
    (net (code "191") (name "unconnected-(U5-PadA11)") (class "Default")
      (node (ref "U5") (pin "A11") (pinfunction "A11_A11") (pintype "bidirectional"))
    )
    (net (code "192") (name "unconnected-(U5-PadA12)") (class "Default")
      (node (ref "U5") (pin "A12") (pinfunction "A12_A12") (pintype "bidirectional"))
    )
    (net (code "193") (name "unconnected-(U5-PadA13)") (class "Default")
      (node (ref "U5") (pin "A13") (pinfunction "A13_A13") (pintype "bidirectional"))
    )
    (net (code "194") (name "unconnected-(U5-PadA14)") (class "Default")
      (node (ref "U5") (pin "A14") (pinfunction "A14_A14") (pintype "bidirectional"))
    )
    (net (code "195") (name "unconnected-(U5-PadA15)") (class "Default")
      (node (ref "U5") (pin "A15") (pinfunction "A15_A15") (pintype "bidirectional"))
    )
    (net (code "196") (name "unconnected-(U5-PadAREF)") (class "Default")
      (node (ref "U5") (pin "AREF") (pinfunction "AREF_AREF") (pintype "bidirectional"))
    )
    (net (code "197") (name "unconnected-(U5-PadRESET)") (class "Default")
      (node (ref "U5") (pin "RESET") (pinfunction "RESET_RESET") (pintype "bidirectional"))
    )
    (net (code "198") (name "unconnected-(U5-PadVIN)") (class "Default")
      (node (ref "U5") (pin "VIN") (pinfunction "VIN_VIN") (pintype "bidirectional"))
    )
  )
)
